# midi_block.net
KiCad netlist of a schematic drawn in EAGLE
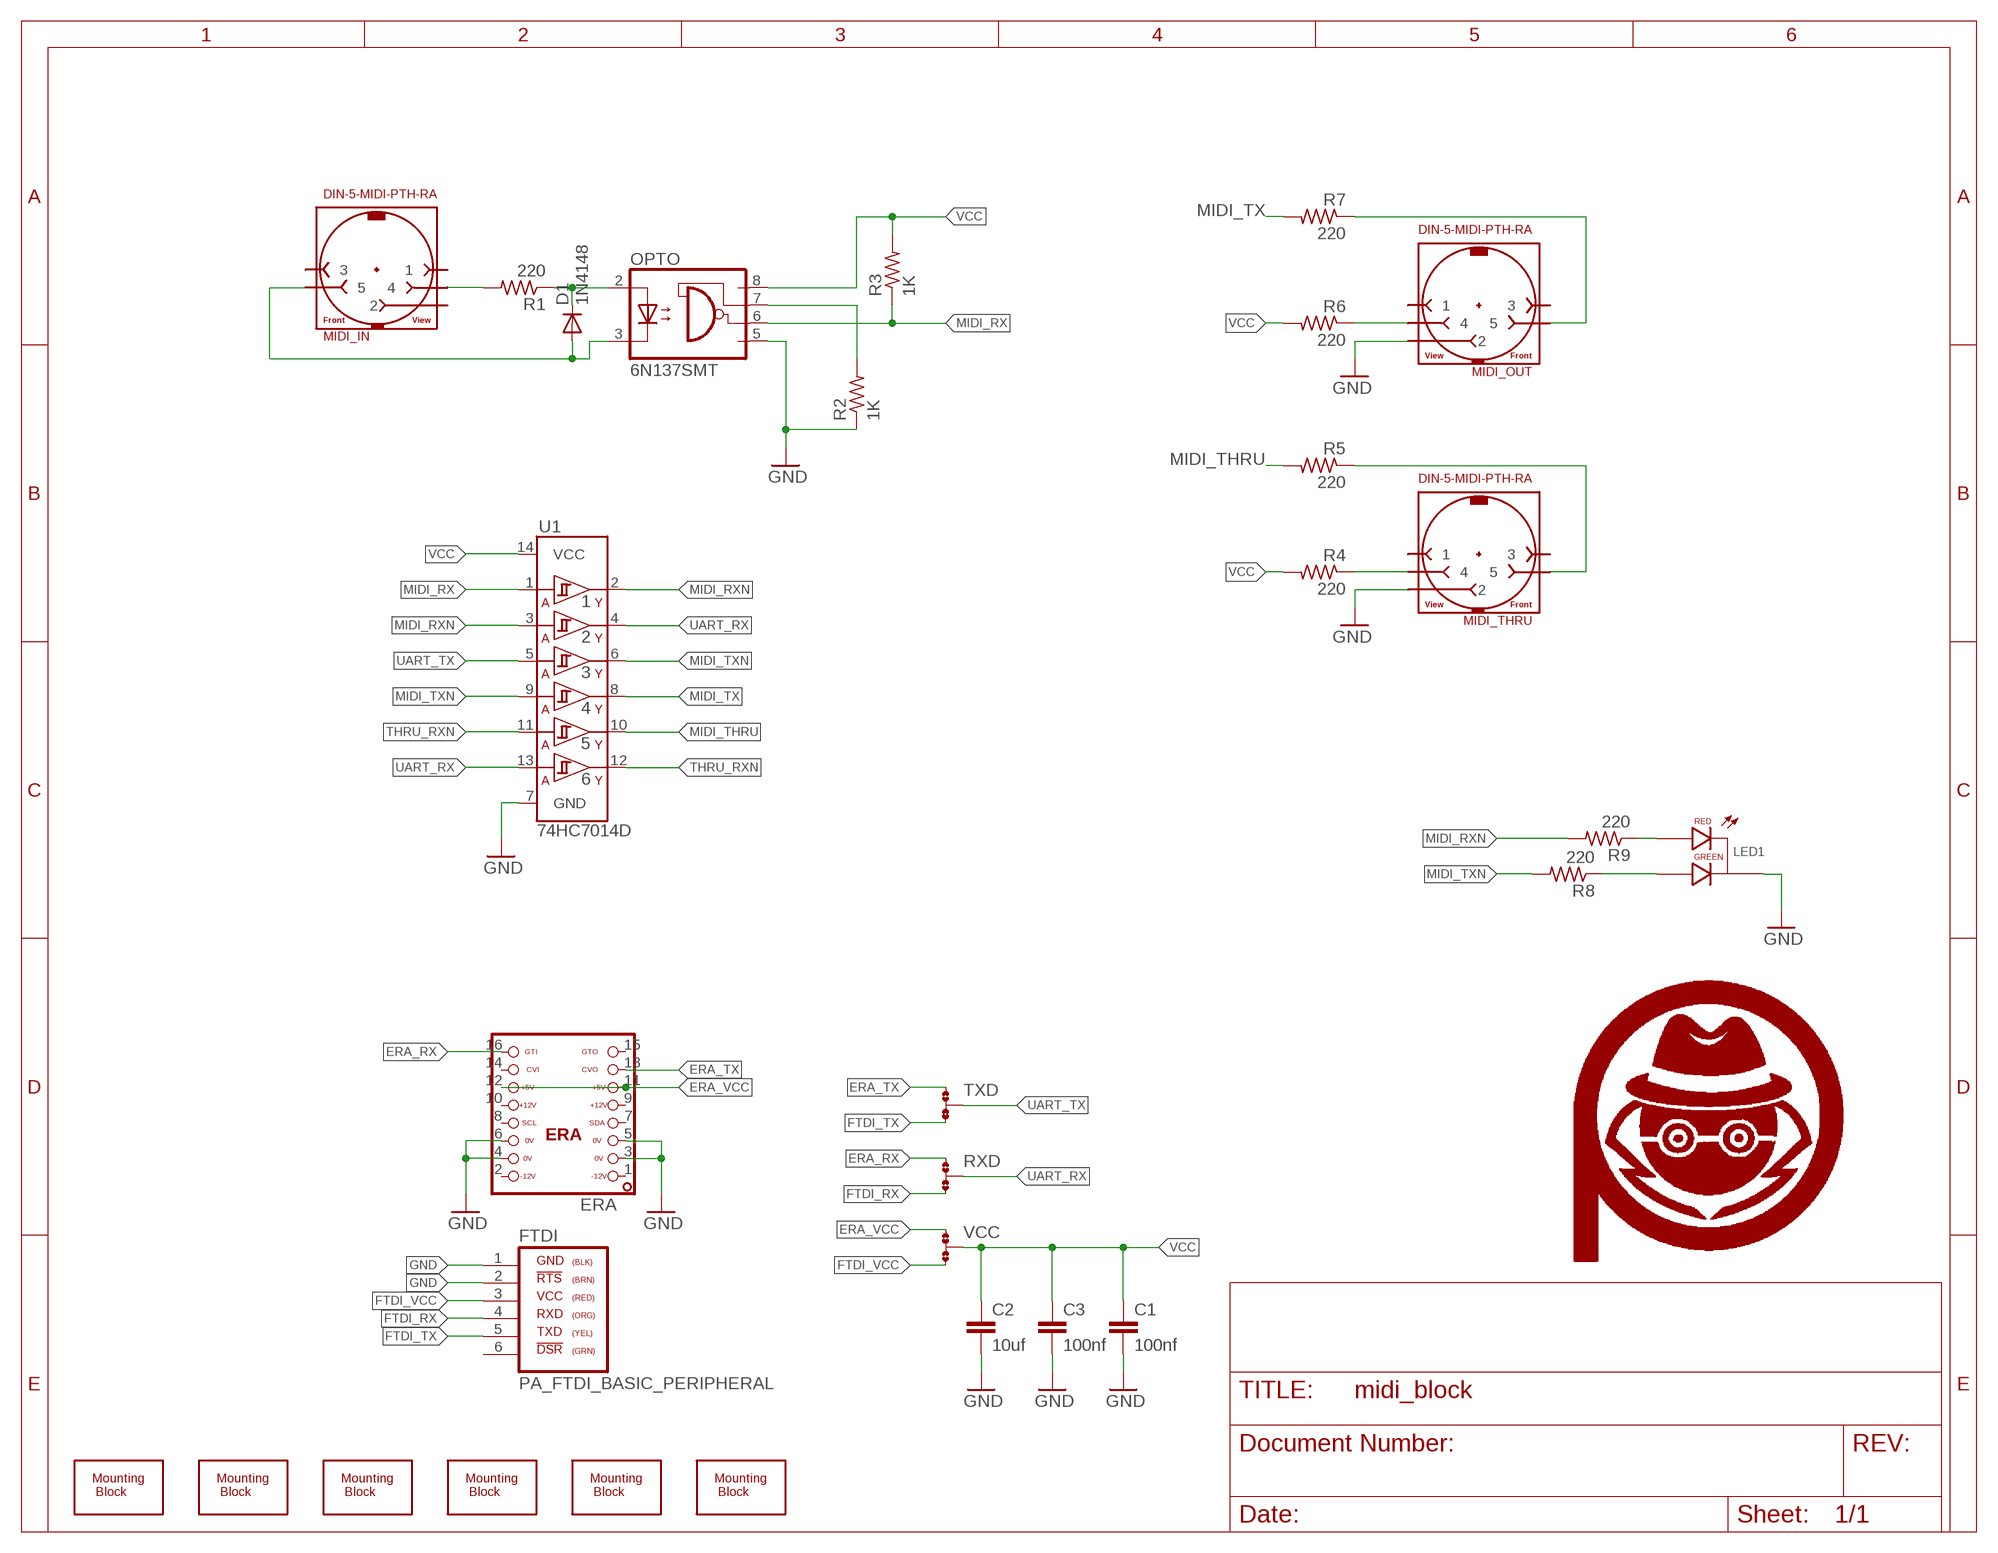
[diagram p0: schematic, sheet 1]

(export (version "E")
  (design (tool "Eeschema 10.0.6"))
  (components
    (comp (ref "C1")
      (value "100nf")
      (footprint "eagle-import:0603-CAP")
      (libsource (lib "eagle-import") (part "CAP0603-CAP"))
    )
    (comp (ref "C2")
      (value "10uf")
      (footprint "eagle-import:0603-CAP")
      (libsource (lib "eagle-import") (part "CAP0603-CAP"))
    )
    (comp (ref "C3")
      (value "100nf")
      (footprint "eagle-import:0603-CAP")
      (libsource (lib "eagle-import") (part "CAP0603-CAP"))
    )
    (comp (ref "D1")
      (value "1N4148")
      (footprint "eagle-import:SOD323-W")
      (libsource (lib "eagle-import") (part "DIODE-SOD323-W"))
    )
    (comp (ref "ERA")
      (value "ERA-SHROUD")
      (footprint "eagle-import:ERA")
      (libsource (lib "eagle-import") (part "ERA-SHROUD"))
    )
    (comp (ref "FTDI")
      (value "PA_FTDI_BASIC_PERIPHERAL")
      (footprint "eagle-import:PA_PMOD_SIL_MALE")
      (libsource (lib "eagle-import") (part "PA_FTDI_BASIC_PERIPHERAL"))
    )
    (comp (ref "LED1")
      (value "LED-RG-CC-PTH-G18500")
      (footprint "eagle-import:LED-RG-PANEL")
      (libsource (lib "eagle-import") (part "LED-RG-CC-PTH-G18500"))
    )
    (comp (ref "MIDI_IN")
      (value "DIN-5-MIDI-PTH-RA")
      (footprint "eagle-import:DIN-5-PTH-RA-SUPPORT")
      (libsource (lib "eagle-import") (part "DIN-5-MIDI-PTH-RA"))
    )
    (comp (ref "MIDI_OUT")
      (value "DIN-5-MIDI-PTH-RA")
      (footprint "eagle-import:DIN-5-PTH-RA-SUPPORT")
      (libsource (lib "eagle-import") (part "DIN-5-MIDI-PTH-RA"))
    )
    (comp (ref "MIDI_THRU")
      (value "DIN-5-MIDI-PTH-RA")
      (footprint "eagle-import:DIN-5-PTH-RA-SUPPORT")
      (libsource (lib "eagle-import") (part "DIN-5-MIDI-PTH-RA"))
    )
    (comp (ref "OPTO")
      (value "6N137SMT")
      (footprint "eagle-import:DIL8-SMD")
      (libsource (lib "eagle-import") (part "6N137SMT"))
    )
    (comp (ref "R1")
      (value "220")
      (footprint "eagle-import:R0603")
      (libsource (lib "eagle-import") (part "R-US_R0603"))
    )
    (comp (ref "R2")
      (value "1K")
      (footprint "eagle-import:R0603")
      (libsource (lib "eagle-import") (part "R-US_R0603"))
    )
    (comp (ref "R3")
      (value "1K")
      (footprint "eagle-import:R0603")
      (libsource (lib "eagle-import") (part "R-US_R0603"))
    )
    (comp (ref "R4")
      (value "220")
      (footprint "eagle-import:R0603")
      (libsource (lib "eagle-import") (part "R-US_R0603"))
    )
    (comp (ref "R5")
      (value "220")
      (footprint "eagle-import:R0603")
      (libsource (lib "eagle-import") (part "R-US_R0603"))
    )
    (comp (ref "R6")
      (value "220")
      (footprint "eagle-import:R0603")
      (libsource (lib "eagle-import") (part "R-US_R0603"))
    )
    (comp (ref "R7")
      (value "220")
      (footprint "eagle-import:R0603")
      (libsource (lib "eagle-import") (part "R-US_R0603"))
    )
    (comp (ref "R8")
      (value "220")
      (footprint "eagle-import:R0603")
      (libsource (lib "eagle-import") (part "R-US_R0603"))
    )
    (comp (ref "R9")
      (value "220")
      (footprint "eagle-import:R0603")
      (libsource (lib "eagle-import") (part "R-US_R0603"))
    )
    (comp (ref "RXD")
      (value "JMP-3-NO-PTH")
      (footprint "eagle-import:JMP-3-NO-PTH-2.54")
      (libsource (lib "eagle-import") (part "JMP-3-NO-PTH"))
    )
    (comp (ref "TXD")
      (value "JMP-3-NO-PTH")
      (footprint "eagle-import:JMP-3-NO-PTH-2.54")
      (libsource (lib "eagle-import") (part "JMP-3-NO-PTH"))
    )
    (comp (ref "U$1")
      (value "PCB-MB-SIDE")
      (footprint "eagle-import:PCB-MB-01-SIDE")
      (libsource (lib "eagle-import") (part "PCB-MB-SIDE"))
    )
    (comp (ref "U$2")
      (value "PCB-MB-SIDE")
      (footprint "eagle-import:PCB-MB-01-SIDE")
      (libsource (lib "eagle-import") (part "PCB-MB-SIDE"))
    )
    (comp (ref "U$3")
      (value "PCB-MB-SIDE")
      (footprint "eagle-import:PCB-MB-01-SIDE")
      (libsource (lib "eagle-import") (part "PCB-MB-SIDE"))
    )
    (comp (ref "U$4")
      (value "PCB-MB-SIDE")
      (footprint "eagle-import:PCB-MB-01-SIDE")
      (libsource (lib "eagle-import") (part "PCB-MB-SIDE"))
    )
    (comp (ref "U$5")
      (value "PA_LOGO_SYMMED")
      (footprint "eagle-import:PA_LOGO_AGENT_MED_SYM")
      (libsource (lib "eagle-import") (part "PA_LOGO_SYMMED"))
    )
    (comp (ref "U$6")
      (value "PA_LOGO_SYMMED")
      (footprint "eagle-import:PA_LOGO_AGENT_MED_SYM")
      (libsource (lib "eagle-import") (part "PA_LOGO_SYMMED"))
    )
    (comp (ref "U$7")
      (value "PCB-MB-SIDE")
      (footprint "eagle-import:PCB-MB-01-SIDE")
      (libsource (lib "eagle-import") (part "PCB-MB-SIDE"))
    )
    (comp (ref "U$8")
      (value "PCB-MB-SIDE")
      (footprint "eagle-import:PCB-MB-01-SIDE")
      (libsource (lib "eagle-import") (part "PCB-MB-SIDE"))
    )
    (comp (ref "U1")
      (value "74HC7014D")
      (footprint "eagle-import:SOIC-14")
      (libsource (lib "eagle-import") (part "74HC7014D"))
    )
    (comp (ref "VCC")
      (value "JMP-3-NO-PTH")
      (footprint "eagle-import:JMP-3-NO-PTH-2.54")
      (libsource (lib "eagle-import") (part "JMP-3-NO-PTH"))
    )
  )
  (nets
    (net (code "1") (name "ERA_RX") (class "Default")
      (node (ref "ERA") (pin "16") (pinfunction "16_16") (pintype "passive"))
      (node (ref "RXD") (pin "1") (pinfunction "1_1") (pintype "passive"))
    )
    (net (code "2") (name "ERA_TX") (class "Default")
      (node (ref "ERA") (pin "13") (pinfunction "13_13") (pintype "passive"))
      (node (ref "TXD") (pin "1") (pinfunction "1_1") (pintype "passive"))
    )
    (net (code "3") (name "ERA_VCC") (class "Default")
      (node (ref "ERA") (pin "11") (pinfunction "11_11") (pintype "passive"))
      (node (ref "ERA") (pin "12") (pinfunction "12_12") (pintype "passive"))
      (node (ref "VCC") (pin "1") (pinfunction "1_1") (pintype "passive"))
    )
    (net (code "4") (name "FTDI_RX") (class "Default")
      (node (ref "FTDI") (pin "4") (pinfunction "4_4") (pintype "passive"))
      (node (ref "RXD") (pin "3") (pinfunction "3_3") (pintype "passive"))
    )
    (net (code "5") (name "FTDI_TX") (class "Default")
      (node (ref "FTDI") (pin "5") (pinfunction "5_5") (pintype "passive"))
      (node (ref "TXD") (pin "3") (pinfunction "3_3") (pintype "passive"))
    )
    (net (code "6") (name "FTDI_VCC") (class "Default")
      (node (ref "FTDI") (pin "3") (pinfunction "3_3") (pintype "passive"))
      (node (ref "VCC") (pin "3") (pinfunction "3_3") (pintype "passive"))
    )
    (net (code "7") (name "GND") (class "Default")
      (node (ref "C1") (pin "2") (pinfunction "2_2") (pintype "passive"))
      (node (ref "C2") (pin "2") (pinfunction "2_2") (pintype "passive"))
      (node (ref "C3") (pin "2") (pinfunction "2_2") (pintype "passive"))
      (node (ref "ERA") (pin "3") (pinfunction "3_3") (pintype "passive"))
      (node (ref "ERA") (pin "4") (pinfunction "4_4") (pintype "passive"))
      (node (ref "ERA") (pin "5") (pinfunction "5_5") (pintype "passive"))
      (node (ref "ERA") (pin "6") (pinfunction "6_6") (pintype "passive"))
      (node (ref "FTDI") (pin "1") (pinfunction "1_1") (pintype "passive"))
      (node (ref "FTDI") (pin "2") (pinfunction "2_2") (pintype "passive"))
      (node (ref "LED1") (pin "CC") (pinfunction "CATHODE_CC") (pintype "bidirectional"))
      (node (ref "MIDI_OUT") (pin "2") (pinfunction "2_2") (pintype "bidirectional"))
      (node (ref "MIDI_THRU") (pin "2") (pinfunction "2_2") (pintype "bidirectional"))
      (node (ref "OPTO") (pin "5") (pinfunction "GND_5") (pintype "passive"))
      (node (ref "R2") (pin "1") (pinfunction "1_1") (pintype "passive"))
      (node (ref "U1") (pin "7") (pinfunction "GND_7") (pintype "power_in"))
    )
    (net (code "8") (name "MIDI_RX") (class "Default")
      (node (ref "OPTO") (pin "6") (pinfunction "VO_6") (pintype "passive"))
      (node (ref "R3") (pin "1") (pinfunction "1_1") (pintype "passive"))
      (node (ref "U1") (pin "1") (pinfunction "1A_1") (pintype "input"))
    )
    (net (code "9") (name "MIDI_RXN") (class "Default")
      (node (ref "R9") (pin "2") (pinfunction "2_2") (pintype "passive"))
      (node (ref "U1") (pin "2") (pinfunction "1Y_2") (pintype "output"))
      (node (ref "U1") (pin "3") (pinfunction "2A_3") (pintype "input"))
    )
    (net (code "10") (name "MIDI_THRU") (class "Default")
      (node (ref "R5") (pin "2") (pinfunction "2_2") (pintype "passive"))
      (node (ref "U1") (pin "10") (pinfunction "5Y_10") (pintype "output"))
    )
    (net (code "11") (name "MIDI_TX") (class "Default")
      (node (ref "R7") (pin "2") (pinfunction "2_2") (pintype "passive"))
      (node (ref "U1") (pin "8") (pinfunction "4Y_8") (pintype "output"))
    )
    (net (code "12") (name "MIDI_TXN") (class "Default")
      (node (ref "R8") (pin "2") (pinfunction "2_2") (pintype "passive"))
      (node (ref "U1") (pin "6") (pinfunction "3Y_6") (pintype "output"))
      (node (ref "U1") (pin "9") (pinfunction "4A_9") (pintype "input"))
    )
    (net (code "13") (name "Net-(LED1-GREEN_CATHODE)") (class "Default")
      (node (ref "LED1") (pin "GREEN") (pinfunction "GREEN_CATHODE_GREEN") (pintype "bidirectional"))
      (node (ref "R8") (pin "1") (pinfunction "1_1") (pintype "passive"))
    )
    (net (code "14") (name "Net-(LED1-RED_CATHODE)") (class "Default")
      (node (ref "LED1") (pin "RED") (pinfunction "RED_CATHODE_RED") (pintype "bidirectional"))
      (node (ref "R9") (pin "1") (pinfunction "1_1") (pintype "passive"))
    )
    (net (code "15") (name "Net-(MIDI_IN-Pad4)") (class "Default")
      (node (ref "MIDI_IN") (pin "4") (pinfunction "4_4") (pintype "bidirectional"))
      (node (ref "R1") (pin "2") (pinfunction "2_2") (pintype "passive"))
    )
    (net (code "16") (name "Net-(MIDI_OUT-Pad4)") (class "Default")
      (node (ref "MIDI_OUT") (pin "4") (pinfunction "4_4") (pintype "bidirectional"))
      (node (ref "R6") (pin "1") (pinfunction "1_1") (pintype "passive"))
    )
    (net (code "17") (name "Net-(MIDI_OUT-Pad5)") (class "Default")
      (node (ref "MIDI_OUT") (pin "5") (pinfunction "5_5") (pintype "bidirectional"))
      (node (ref "R7") (pin "1") (pinfunction "1_1") (pintype "passive"))
    )
    (net (code "18") (name "Net-(MIDI_THRU-Pad4)") (class "Default")
      (node (ref "MIDI_THRU") (pin "4") (pinfunction "4_4") (pintype "bidirectional"))
      (node (ref "R4") (pin "1") (pinfunction "1_1") (pintype "passive"))
    )
    (net (code "19") (name "Net-(MIDI_THRU-Pad5)") (class "Default")
      (node (ref "MIDI_THRU") (pin "5") (pinfunction "5_5") (pintype "bidirectional"))
      (node (ref "R5") (pin "1") (pinfunction "1_1") (pintype "passive"))
    )
    (net (code "20") (name "Net-(OPTO-A)") (class "Default")
      (node (ref "D1") (pin "C") (pinfunction "C_C") (pintype "passive"))
      (node (ref "OPTO") (pin "2") (pinfunction "A_2") (pintype "passive"))
      (node (ref "R1") (pin "1") (pinfunction "1_1") (pintype "passive"))
    )
    (net (code "21") (name "Net-(OPTO-C)") (class "Default")
      (node (ref "D1") (pin "A") (pinfunction "A_A") (pintype "passive"))
      (node (ref "MIDI_IN") (pin "5") (pinfunction "5_5") (pintype "bidirectional"))
      (node (ref "OPTO") (pin "3") (pinfunction "C_3") (pintype "passive"))
    )
    (net (code "22") (name "Net-(OPTO-VE)") (class "Default")
      (node (ref "OPTO") (pin "7") (pinfunction "VE_7") (pintype "passive"))
      (node (ref "R2") (pin "2") (pinfunction "2_2") (pintype "passive"))
    )
    (net (code "23") (name "THRU_RXN") (class "Default")
      (node (ref "U1") (pin "11") (pinfunction "5A_11") (pintype "input"))
      (node (ref "U1") (pin "12") (pinfunction "6Y_12") (pintype "output"))
    )
    (net (code "24") (name "UART_RX") (class "Default")
      (node (ref "RXD") (pin "2") (pinfunction "2_2") (pintype "passive"))
      (node (ref "U1") (pin "13") (pinfunction "6A_13") (pintype "input"))
      (node (ref "U1") (pin "4") (pinfunction "2Y_4") (pintype "output"))
    )
    (net (code "25") (name "UART_TX") (class "Default")
      (node (ref "TXD") (pin "2") (pinfunction "2_2") (pintype "passive"))
      (node (ref "U1") (pin "5") (pinfunction "3A_5") (pintype "input"))
    )
    (net (code "26") (name "VCC") (class "Default")
      (node (ref "C1") (pin "1") (pinfunction "1_1") (pintype "passive"))
      (node (ref "C2") (pin "1") (pinfunction "1_1") (pintype "passive"))
      (node (ref "C3") (pin "1") (pinfunction "1_1") (pintype "passive"))
      (node (ref "OPTO") (pin "8") (pinfunction "VCC_8") (pintype "passive"))
      (node (ref "R3") (pin "2") (pinfunction "2_2") (pintype "passive"))
      (node (ref "R4") (pin "2") (pinfunction "2_2") (pintype "passive"))
      (node (ref "R6") (pin "2") (pinfunction "2_2") (pintype "passive"))
      (node (ref "U1") (pin "14") (pinfunction "VCC_14") (pintype "power_in"))
      (node (ref "VCC") (pin "2") (pinfunction "2_2") (pintype "passive"))
    )
    (net (code "27") (name "unconnected-(ERA-Pad1)") (class "Default")
      (node (ref "ERA") (pin "1") (pinfunction "1_1") (pintype "passive"))
    )
    (net (code "28") (name "unconnected-(ERA-Pad2)") (class "Default")
      (node (ref "ERA") (pin "2") (pinfunction "2_2") (pintype "passive"))
    )
    (net (code "29") (name "unconnected-(ERA-Pad7)") (class "Default")
      (node (ref "ERA") (pin "7") (pinfunction "7_7") (pintype "passive"))
    )
    (net (code "30") (name "unconnected-(ERA-Pad8)") (class "Default")
      (node (ref "ERA") (pin "8") (pinfunction "8_8") (pintype "passive"))
    )
    (net (code "31") (name "unconnected-(ERA-Pad9)") (class "Default")
      (node (ref "ERA") (pin "9") (pinfunction "9_9") (pintype "passive"))
    )
    (net (code "32") (name "unconnected-(ERA-Pad10)") (class "Default")
      (node (ref "ERA") (pin "10") (pinfunction "10_10") (pintype "passive"))
    )
    (net (code "33") (name "unconnected-(ERA-Pad14)") (class "Default")
      (node (ref "ERA") (pin "14") (pinfunction "14_14") (pintype "passive"))
    )
    (net (code "34") (name "unconnected-(ERA-Pad15)") (class "Default")
      (node (ref "ERA") (pin "15") (pinfunction "15_15") (pintype "passive"))
    )
    (net (code "35") (name "unconnected-(FTDI-Pad6)") (class "Default")
      (node (ref "FTDI") (pin "6") (pinfunction "6_6") (pintype "passive"))
    )
    (net (code "36") (name "unconnected-(MIDI_IN-Pad1)") (class "Default")
      (node (ref "MIDI_IN") (pin "1") (pinfunction "1_1") (pintype "bidirectional"))
    )
    (net (code "37") (name "unconnected-(MIDI_IN-Pad2)") (class "Default")
      (node (ref "MIDI_IN") (pin "2") (pinfunction "2_2") (pintype "bidirectional"))
    )
    (net (code "38") (name "unconnected-(MIDI_IN-Pad3)") (class "Default")
      (node (ref "MIDI_IN") (pin "3") (pinfunction "3_3") (pintype "bidirectional"))
    )
    (net (code "39") (name "unconnected-(MIDI_OUT-Pad1)") (class "Default")
      (node (ref "MIDI_OUT") (pin "1") (pinfunction "1_1") (pintype "bidirectional"))
    )
    (net (code "40") (name "unconnected-(MIDI_OUT-Pad3)") (class "Default")
      (node (ref "MIDI_OUT") (pin "3") (pinfunction "3_3") (pintype "bidirectional"))
    )
    (net (code "41") (name "unconnected-(MIDI_THRU-Pad1)") (class "Default")
      (node (ref "MIDI_THRU") (pin "1") (pinfunction "1_1") (pintype "bidirectional"))
    )
    (net (code "42") (name "unconnected-(MIDI_THRU-Pad3)") (class "Default")
      (node (ref "MIDI_THRU") (pin "3") (pinfunction "3_3") (pintype "bidirectional"))
    )
  )
)
